# Display.net
KiCad netlist of a schematic drawn in Altium Designer
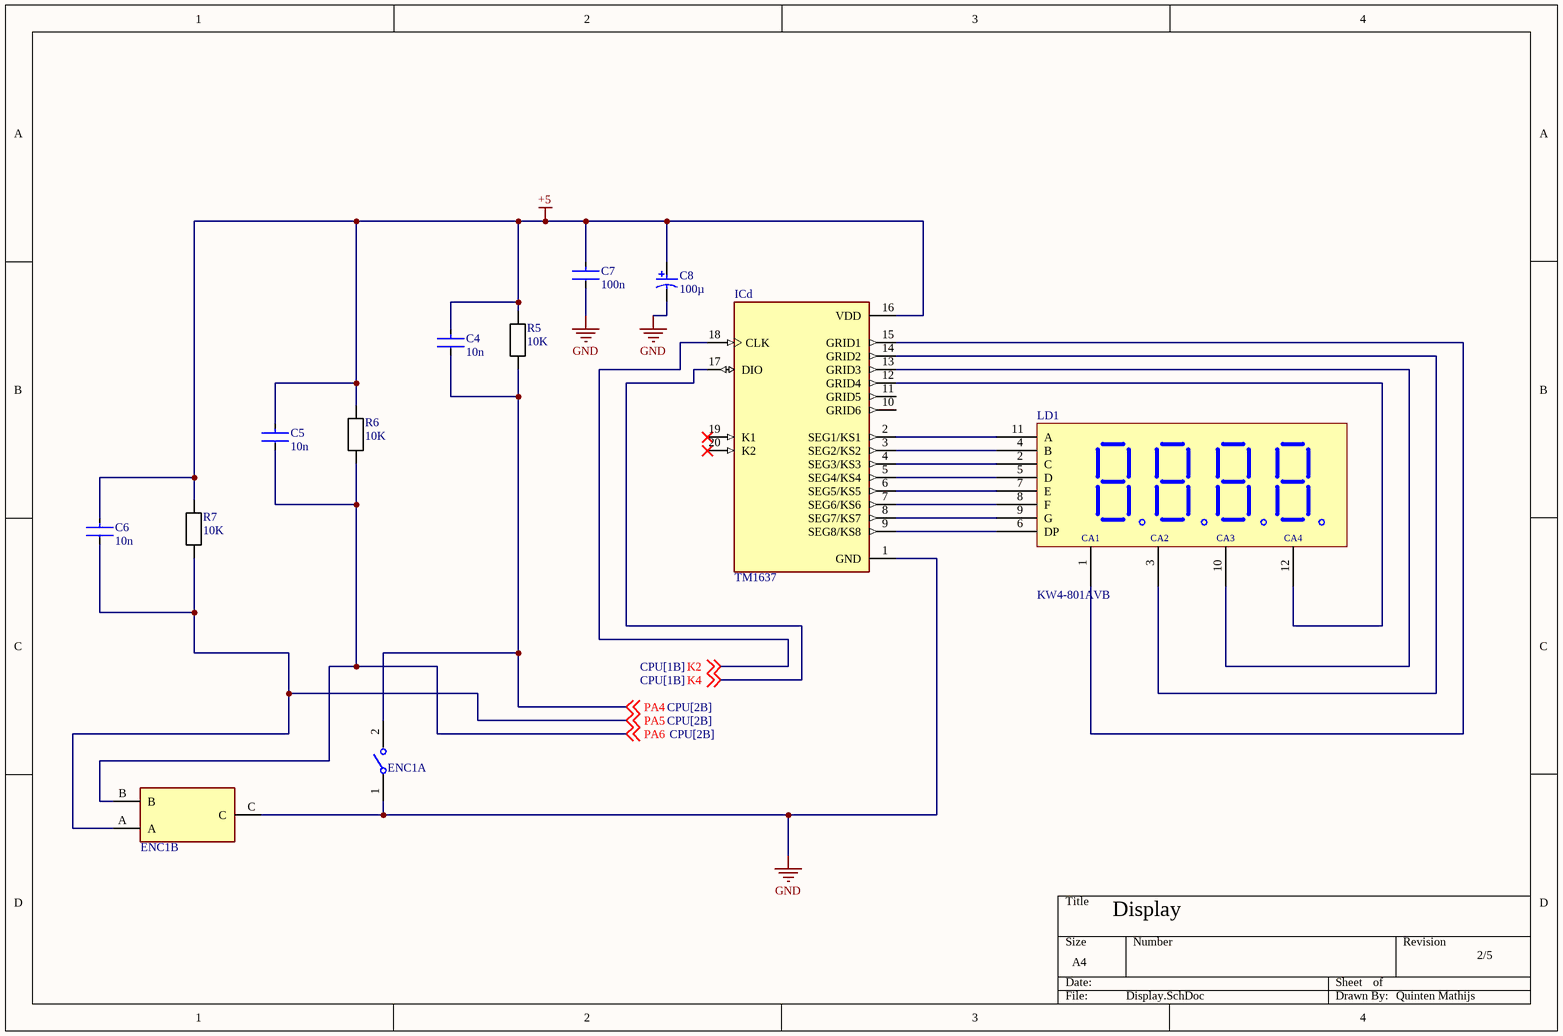
[diagram p0: Display.SchDoc]

(export (version "E")
  (design (tool "Eeschema 10.0.6"))
  (components
    (comp (ref "C4")
      (value "10n")
      (footprint "CC_0805_L")
      (fields
        (field (name "MANUFACTURER") "KEMET")
        (field (name "OCTOPART") "https://octopart.com/c0805c224k5ractu-kemet-144670")
        (field (name "MANUFACTURER PART NUMBER") "C0805C224K5RACTU")
      )
      (libsource (lib "Schem_Soldeerstation") (part "Capacitor_Ceramic"))
    )
    (comp (ref "C5")
      (value "10n")
      (footprint "CC_0805_L")
      (fields
        (field (name "MANUFACTURER") "KEMET")
        (field (name "OCTOPART") "https://octopart.com/c0805c224k5ractu-kemet-144670")
        (field (name "MANUFACTURER PART NUMBER") "C0805C224K5RACTU")
      )
      (libsource (lib "Schem_Soldeerstation") (part "Capacitor_Ceramic"))
    )
    (comp (ref "C6")
      (value "10n")
      (footprint "CC_0805_L")
      (fields
        (field (name "MANUFACTURER") "KEMET")
        (field (name "OCTOPART") "https://octopart.com/c0805c224k5ractu-kemet-144670")
        (field (name "MANUFACTURER PART NUMBER") "C0805C224K5RACTU")
      )
      (libsource (lib "Schem_Soldeerstation") (part "Capacitor_Ceramic"))
    )
    (comp (ref "C7")
      (value "100n")
      (footprint "CC_0805_L")
      (fields
        (field (name "MANUFACTURER") "KEMET")
        (field (name "OCTOPART") "https://octopart.com/c0805c224k5ractu-kemet-144670")
        (field (name "MANUFACTURER PART NUMBER") "C0805C224K5RACTU")
      )
      (libsource (lib "Schem_Soldeerstation") (part "Capacitor_Ceramic"))
    )
    (comp (ref "C8")
      (value "100µ")
      (footprint "CE_D8_L10")
      (fields (field (name "MANUFACTURER") "Panasonic"))
      (libsource (lib "Schem_Soldeerstation") (part "Capacitor_Electrolytic"))
    )
    (comp (ref "ENC1")
      (value "PEC11R-4220F-S0012")
      (footprint "PEC11R_4220F_S0012")
      (description "ROTARY ENCODER MECHANICAL 12PPR")
      (libsource (lib "") (part "PEC11R-4220F-S0012_1"))
    )
    (comp (ref "ICd")
      (value "TM1637")
      (footprint "SOP_20_M")
      (description "LED Drive Control Special Circuit")
      (fields (field (name "MF") "Titan Micro Electronics"))
      (libsource (lib "Schem_Soldeerstation") (part "TM1637"))
    )
    (comp (ref "LD1")
      (value "KW4-801AVB")
      (footprint "7-Segment")
      (description "4-Digit LED Display")
      (libsource (lib "Schem_Soldeerstation") (part "KW4-801AVB"))
    )
    (comp (ref "R5")
      (value "10K")
      (footprint "R_0805_L")
      (description "Resistor")
      (fields (field (name "MANUFACTURER") "Vishay Dale") (field (name "PART NUMBER") "CRCW08050000Z0EA"))
      (libsource (lib "Schem_Soldeerstation") (part "0805 (Resistor)"))
    )
    (comp (ref "R6")
      (value "10K")
      (footprint "R_0805_L")
      (description "Resistor")
      (fields (field (name "MANUFACTURER") "Vishay Dale") (field (name "PART NUMBER") "CRCW08050000Z0EA"))
      (libsource (lib "Schem_Soldeerstation") (part "0805 (Resistor)"))
    )
    (comp (ref "R7")
      (value "10K")
      (footprint "R_0805_L")
      (description "Resistor")
      (fields (field (name "MANUFACTURER") "Vishay Dale") (field (name "PART NUMBER") "CRCW08050000Z0EA"))
      (libsource (lib "Schem_Soldeerstation") (part "0805 (Resistor)"))
    )
  )
  (nets
    (net (code "1") (name "+5") (class "Default")
      (node (ref "C4") (pin "1") (pinfunction "1_1") (pintype "passive"))
      (node (ref "C5") (pin "1") (pinfunction "1_1") (pintype "passive"))
      (node (ref "C6") (pin "1") (pinfunction "1_1") (pintype "passive"))
      (node (ref "C7") (pin "1") (pinfunction "1_1") (pintype "passive"))
      (node (ref "C8") (pin "2") (pinfunction "2_2") (pintype "passive"))
      (node (ref "ICd") (pin "16") (pinfunction "VDD_16") (pintype "power_in"))
      (node (ref "R5") (pin "2") (pinfunction "2_2") (pintype "passive"))
      (node (ref "R6") (pin "2") (pinfunction "2_2") (pintype "passive"))
      (node (ref "R7") (pin "1") (pinfunction "1_1") (pintype "passive"))
    )
    (net (code "2") (name "GND") (class "Default")
      (node (ref "C7") (pin "2") (pinfunction "2_2") (pintype "passive"))
      (node (ref "C8") (pin "1") (pinfunction "1_1") (pintype "passive"))
      (node (ref "ENC1") (pin "1") (pinfunction "1_1") (pintype "passive"))
      (node (ref "ENC1") (pin "C") (pinfunction "C_C") (pintype "passive"))
      (node (ref "ICd") (pin "1") (pinfunction "GND_1") (pintype "power_in"))
    )
    (net (code "3") (name "K2") (class "Default")
      (node (ref "ICd") (pin "18") (pinfunction "CLK_18") (pintype "input"))
    )
    (net (code "4") (name "K4") (class "Default")
      (node (ref "ICd") (pin "17") (pinfunction "DIO_17") (pintype "bidirectional"))
    )
    (net (code "5") (name "Net-(ICd-GRID1)") (class "Default")
      (node (ref "ICd") (pin "15") (pinfunction "GRID1_15") (pintype "output"))
      (node (ref "LD1") (pin "1") (pinfunction "CA1_1") (pintype "passive"))
    )
    (net (code "6") (name "Net-(ICd-GRID2)") (class "Default")
      (node (ref "ICd") (pin "14") (pinfunction "GRID2_14") (pintype "output"))
      (node (ref "LD1") (pin "3") (pinfunction "13_3") (pintype "passive"))
    )
    (net (code "7") (name "Net-(ICd-GRID3)") (class "Default")
      (node (ref "ICd") (pin "13") (pinfunction "GRID3_13") (pintype "output"))
      (node (ref "LD1") (pin "10") (pinfunction "14_10") (pintype "passive"))
    )
    (net (code "8") (name "Net-(ICd-GRID4)") (class "Default")
      (node (ref "ICd") (pin "12") (pinfunction "GRID4_12") (pintype "output"))
      (node (ref "LD1") (pin "12") (pinfunction "15_12") (pintype "passive"))
    )
    (net (code "9") (name "Net-(ICd-SEG1{slash}KS1)") (class "Default")
      (node (ref "ICd") (pin "2") (pinfunction "SEG1/KS1_2") (pintype "output"))
      (node (ref "LD1") (pin "11") (pinfunction "A_11") (pintype "passive"))
    )
    (net (code "10") (name "Net-(ICd-SEG2{slash}KS2)") (class "Default")
      (node (ref "ICd") (pin "3") (pinfunction "SEG2/KS2_3") (pintype "output"))
      (node (ref "LD1") (pin "4") (pinfunction "B_4") (pintype "passive"))
    )
    (net (code "11") (name "Net-(ICd-SEG3{slash}KS3)") (class "Default")
      (node (ref "ICd") (pin "4") (pinfunction "SEG3/KS3_4") (pintype "output"))
      (node (ref "LD1") (pin "2") (pinfunction "C_2") (pintype "passive"))
    )
    (net (code "12") (name "Net-(ICd-SEG4{slash}KS4)") (class "Default")
      (node (ref "ICd") (pin "5") (pinfunction "SEG4/KS4_5") (pintype "output"))
      (node (ref "LD1") (pin "5") (pinfunction "D_5") (pintype "passive"))
    )
    (net (code "13") (name "Net-(ICd-SEG5{slash}KS5)") (class "Default")
      (node (ref "ICd") (pin "6") (pinfunction "SEG5/KS5_6") (pintype "output"))
      (node (ref "LD1") (pin "7") (pinfunction "E_7") (pintype "passive"))
    )
    (net (code "14") (name "Net-(ICd-SEG6{slash}KS6)") (class "Default")
      (node (ref "ICd") (pin "7") (pinfunction "SEG6/KS6_7") (pintype "output"))
      (node (ref "LD1") (pin "8") (pinfunction "F_8") (pintype "passive"))
    )
    (net (code "15") (name "Net-(ICd-SEG7{slash}KS7)") (class "Default")
      (node (ref "ICd") (pin "8") (pinfunction "SEG7/KS7_8") (pintype "output"))
      (node (ref "LD1") (pin "9") (pinfunction "G_9") (pintype "passive"))
    )
    (net (code "16") (name "Net-(ICd-SEG8{slash}KS8)") (class "Default")
      (node (ref "ICd") (pin "9") (pinfunction "SEG8/KS8_9") (pintype "output"))
      (node (ref "LD1") (pin "6") (pinfunction "DP_6") (pintype "passive"))
    )
    (net (code "17") (name "PA4") (class "Default")
      (node (ref "C4") (pin "2") (pinfunction "2_2") (pintype "passive"))
      (node (ref "ENC1") (pin "2") (pinfunction "2_2") (pintype "passive"))
      (node (ref "R5") (pin "1") (pinfunction "1_1") (pintype "passive"))
    )
    (net (code "18") (name "PA5") (class "Default")
      (node (ref "C6") (pin "2") (pinfunction "2_2") (pintype "passive"))
      (node (ref "ENC1") (pin "A") (pinfunction "A_A") (pintype "passive"))
      (node (ref "R7") (pin "2") (pinfunction "2_2") (pintype "passive"))
    )
    (net (code "19") (name "PA6") (class "Default")
      (node (ref "C5") (pin "2") (pinfunction "2_2") (pintype "passive"))
      (node (ref "ENC1") (pin "B") (pinfunction "B_B") (pintype "passive"))
      (node (ref "R6") (pin "1") (pinfunction "1_1") (pintype "passive"))
    )
    (net (code "20") (name "unconnected-(ICd-GRID5-Pad11)") (class "Default")
      (node (ref "ICd") (pin "11") (pinfunction "GRID5_11") (pintype "output"))
    )
    (net (code "21") (name "unconnected-(ICd-GRID6-Pad10)") (class "Default")
      (node (ref "ICd") (pin "10") (pinfunction "GRID6_10") (pintype "output"))
    )
    (net (code "22") (name "unconnected-(ICd-K1-Pad19)") (class "Default")
      (node (ref "ICd") (pin "19") (pinfunction "K1_19") (pintype "input+no_connect"))
    )
    (net (code "23") (name "unconnected-(ICd-K2-Pad20)") (class "Default")
      (node (ref "ICd") (pin "20") (pinfunction "K2_20") (pintype "input+no_connect"))
    )
  )
)
